# atecc608a-breakout.net
KiCad netlist of a schematic drawn in EAGLE
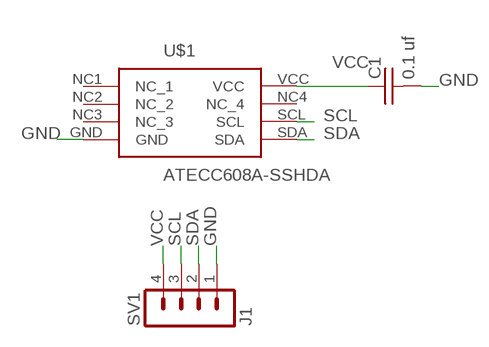
[diagram p0: schematic, sheet 1]

(export (version "E")
  (design (tool "Eeschema 10.0.6"))
  (components
    (comp (ref "C1")
      (value "0.1 uf")
      (footprint "eagle-import:C0805")
      (libsource (lib "eagle-import") (part "C-USC0805"))
    )
    (comp (ref "SV1")
      (value "J1")
      (footprint "eagle-import:MA04-1")
      (libsource (lib "eagle-import") (part "MA04-1"))
    )
    (comp (ref "U$1")
      (value "ATECC608A-SSHDA")
      (footprint "eagle-import:8-SOIC")
      (libsource (lib "eagle-import") (part "ATECC608A-SSHDA"))
    )
  )
  (nets
    (net (code "1") (name "/GND") (class "Default")
      (node (ref "C1") (pin "2") (pinfunction "2_2") (pintype "passive"))
      (node (ref "SV1") (pin "1") (pinfunction "1_1") (pintype "passive"))
      (node (ref "U$1") (pin "GND") (pinfunction "GND_GND") (pintype "power_in"))
    )
    (net (code "2") (name "/SCL") (class "Default")
      (node (ref "SV1") (pin "3") (pinfunction "3_3") (pintype "passive"))
      (node (ref "U$1") (pin "SCL") (pinfunction "SCL_SCL") (pintype "bidirectional"))
    )
    (net (code "3") (name "/SDA") (class "Default")
      (node (ref "SV1") (pin "2") (pinfunction "2_2") (pintype "passive"))
      (node (ref "U$1") (pin "SDA") (pinfunction "SDA_SDA") (pintype "bidirectional"))
    )
    (net (code "4") (name "/VCC") (class "Default")
      (node (ref "C1") (pin "1") (pinfunction "1_1") (pintype "passive"))
      (node (ref "SV1") (pin "4") (pinfunction "4_4") (pintype "passive"))
      (node (ref "U$1") (pin "VCC") (pinfunction "VCC_VCC") (pintype "power_in"))
    )
    (net (code "5") (name "unconnected-(U$1-NC_1-PadNC1)") (class "Default")
      (node (ref "U$1") (pin "NC1") (pinfunction "NC_1_NC1") (pintype "no_connect"))
    )
    (net (code "6") (name "unconnected-(U$1-NC_2-PadNC2)") (class "Default")
      (node (ref "U$1") (pin "NC2") (pinfunction "NC_2_NC2") (pintype "no_connect"))
    )
    (net (code "7") (name "unconnected-(U$1-NC_3-PadNC3)") (class "Default")
      (node (ref "U$1") (pin "NC3") (pinfunction "NC_3_NC3") (pintype "no_connect"))
    )
    (net (code "8") (name "unconnected-(U$1-NC_4-PadNC4)") (class "Default")
      (node (ref "U$1") (pin "NC4") (pinfunction "NC_4_NC4") (pintype "no_connect"))
    )
  )
)
